# powersypply_led.net
KiCad netlist of a schematic drawn in EAGLE
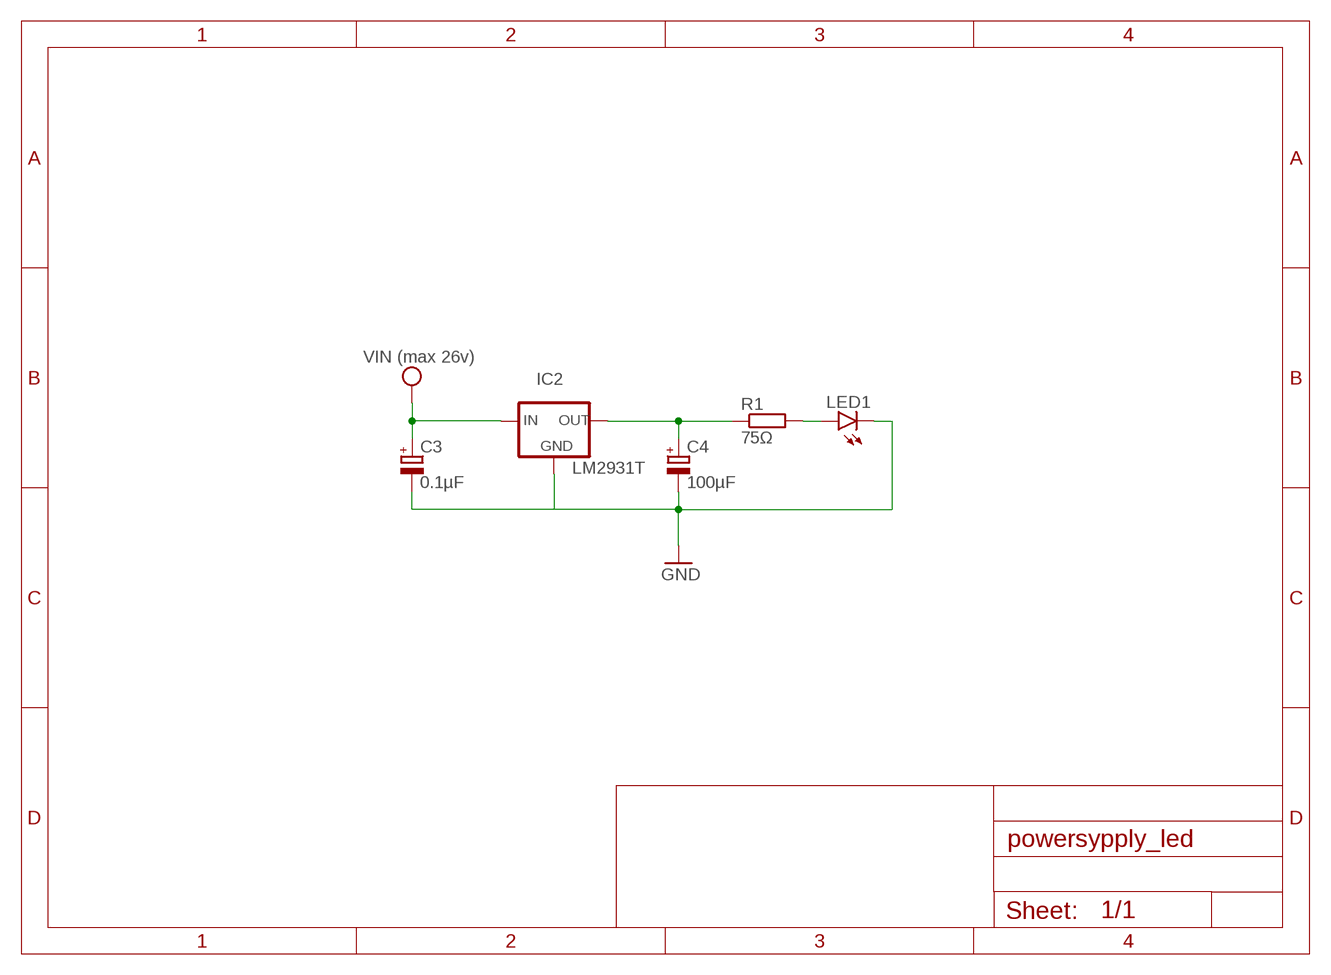
[diagram p0: schematic, sheet 1]

(export (version "E")
  (design (tool "Eeschema 10.0.6"))
  (components
    (comp (ref "C3")
      (value "0.1µF")
      (footprint "eagle-import:E5-5")
      (libsource (lib "eagle-import") (part "CPOL-EUE5-5"))
    )
    (comp (ref "C4")
      (value "100µF")
      (footprint "eagle-import:E5-5")
      (libsource (lib "eagle-import") (part "CPOL-EUE5-5"))
    )
    (comp (ref "IC2")
      (value "LM2931T")
      (footprint "eagle-import:TO220S")
      (libsource (lib "eagle-import") (part "LM2931T"))
    )
    (comp (ref "LED1")
      (value "SFH482")
      (footprint "eagle-import:SFH482")
      (libsource (lib "eagle-import") (part "SFH482"))
    )
    (comp (ref "R1")
      (value "75Ω")
      (footprint "eagle-import:0617_17")
      (libsource (lib "eagle-import") (part "R-EU_0617/17"))
    )
  )
  (nets
    (net (code "1") (name "GND") (class "Default")
      (node (ref "C3") (pin "-") (pinfunction "-_-") (pintype "passive"))
      (node (ref "C4") (pin "-") (pinfunction "-_-") (pintype "passive"))
      (node (ref "IC2") (pin "2") (pinfunction "GND_2") (pintype "input"))
      (node (ref "LED1") (pin "K") (pinfunction "C_K") (pintype "passive"))
    )
    (net (code "2") (name "Net-(IC2-OUT)") (class "Default")
      (node (ref "C4") (pin "+") (pinfunction "+_+") (pintype "passive"))
      (node (ref "IC2") (pin "3") (pinfunction "OUT_3") (pintype "passive"))
      (node (ref "R1") (pin "1") (pinfunction "1_1") (pintype "passive"))
    )
    (net (code "3") (name "Net-(LED1-PadA)") (class "Default")
      (node (ref "LED1") (pin "A") (pinfunction "A_A") (pintype "passive"))
      (node (ref "R1") (pin "2") (pinfunction "2_2") (pintype "passive"))
    )
    (net (code "4") (name "VIN (max 26v)") (class "Default")
      (node (ref "C3") (pin "+") (pinfunction "+_+") (pintype "passive"))
      (node (ref "IC2") (pin "1") (pinfunction "IN_1") (pintype "input"))
    )
  )
)
